# rx.net
KiCad netlist of a schematic drawn in EAGLE
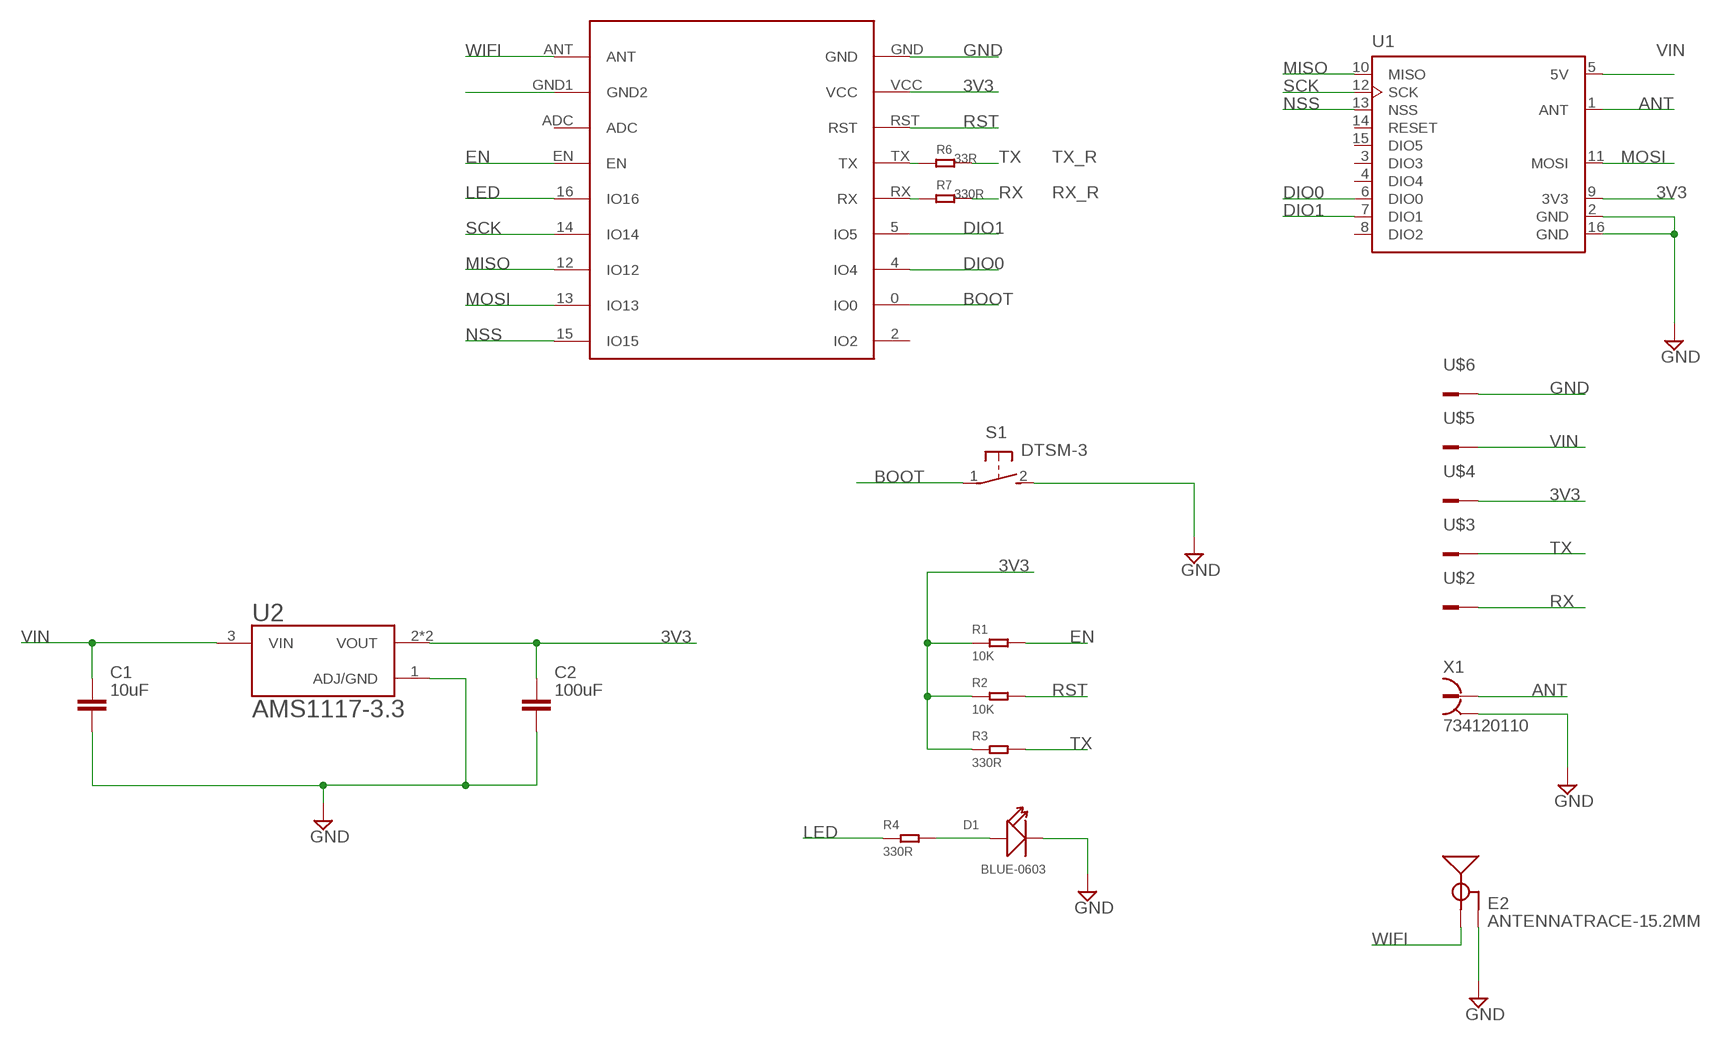
[diagram p0: schematic, sheet 1]

(export (version "E")
  (design (tool "Eeschema 10.0.6"))
  (components
    (comp (ref "C1")
      (value "10uF")
      (footprint "eagle-import:CAPM3528X210")
      (libsource (lib "eagle-import") (part "CTANTALUM-1411(3528-METRIC)_"))
    )
    (comp (ref "C2")
      (value "100uF")
      (footprint "eagle-import:CAPM3528X210")
      (libsource (lib "eagle-import") (part "CTANTALUM-1411(3528-METRIC)_"))
    )
    (comp (ref "D1")
      (value "BLUE-0603")
      (footprint "eagle-import:LED-0603")
      (fields (field (name "MPN") "19-217-BHC-ZL1M2RY-3T"))
      (libsource (lib "eagle-import") (part "SMD-LED-CLEAR-BLUE(0603)"))
    )
    (comp (ref "E2")
      (value "ANTENNATRACE-15.2MM")
      (footprint "eagle-import:TRACE_ANTENNA_2.4GHZ_15.2MM")
      (libsource (lib "eagle-import") (part "ANTENNATRACE-15.2MM"))
    )
    (comp (ref "R1")
      (value "10K")
      (footprint "eagle-import:R0805")
      (fields (field (name "MPN") "RC0805FR-0710KL"))
      (libsource (lib "eagle-import") (part "SMD-RES-10K-1%-1/8W(0805)"))
    )
    (comp (ref "R2")
      (value "10K")
      (footprint "eagle-import:R0805")
      (fields (field (name "MPN") "RC0805FR-0710KL"))
      (libsource (lib "eagle-import") (part "SMD-RES-10K-1%-1/8W(0805)"))
    )
    (comp (ref "R3")
      (value "330R")
      (footprint "eagle-import:R0805")
      (fields (field (name "MPN") "RC0805JR-071KL"))
      (libsource (lib "eagle-import") (part "SMD-RES-330R-5%-1/8W(0805)"))
    )
    (comp (ref "R4")
      (value "330R")
      (footprint "eagle-import:R0805")
      (fields (field (name "MPN") "RC0805JR-071KL"))
      (libsource (lib "eagle-import") (part "SMD-RES-330R-5%-1/8W(0805)"))
    )
    (comp (ref "R6")
      (value "33R")
      (footprint "eagle-import:R0805")
      (fields (field (name "MPN") "RC0805JR-071KL"))
      (libsource (lib "eagle-import") (part "SMD-RES-330R-5%-1/8W(0805)"))
    )
    (comp (ref "R7")
      (value "330R")
      (footprint "eagle-import:R0805")
      (fields (field (name "MPN") "RC0805JR-071KL"))
      (libsource (lib "eagle-import") (part "SMD-RES-330R-5%-1/8W(0805)"))
    )
    (comp (ref "S1")
      (value "DTSM-3")
      (footprint "eagle-import:DTSM-3")
      (libsource (lib "eagle-import") (part "DTSM-3"))
    )
    (comp (ref "U$1")
      (value "ESP-M2")
      (footprint "eagle-import:ESP-M2")
      (fields
        (field (name "MF") "Doctors of Intelligence & Technology Co., LTD")
        (field (name "MP") " ESP-M2 ")
      )
      (libsource (lib "eagle-import") (part "ESP-M2"))
    )
    (comp (ref "U$2")
      (value "CONN-1")
      (footprint "eagle-import:PAD1")
      (libsource (lib "eagle-import") (part "CONN-1"))
    )
    (comp (ref "U$3")
      (value "CONN-1")
      (footprint "eagle-import:PAD1")
      (libsource (lib "eagle-import") (part "CONN-1"))
    )
    (comp (ref "U$4")
      (value "CONN-1")
      (footprint "eagle-import:PAD1")
      (libsource (lib "eagle-import") (part "CONN-1"))
    )
    (comp (ref "U$5")
      (value "CONN-1")
      (footprint "eagle-import:PAD1")
      (libsource (lib "eagle-import") (part "CONN-1"))
    )
    (comp (ref "U$6")
      (value "CONN-1")
      (footprint "eagle-import:PAD1")
      (libsource (lib "eagle-import") (part "CONN-1"))
    )
    (comp (ref "U1")
      (value "RFM95PW-868S2PW")
      (footprint "eagle-import:XCVR_RFM95PW-868S2")
      (libsource (lib "eagle-import") (part "RFM95PW-868S2PW"))
    )
    (comp (ref "U2")
      (value "AMS1117-3.3")
      (footprint "eagle-import:SOT229P700X180-4N")
      (fields (field (name "MF") "Advanced Monolithic Systems"))
      (libsource (lib "eagle-import") (part "AMS1117-3.3"))
    )
    (comp (ref "X1")
      (value "734120110")
      (footprint "eagle-import:734120110")
      (fields (field (name "MF") "Molex") (field (name "MP") "734-12-0110"))
      (libsource (lib "eagle-import") (part "734120110"))
    )
  )
  (nets
    (net (code "1") (name "/3V3") (class "Default")
      (node (ref "C2") (pin "1") (pinfunction "1_1") (pintype "passive"))
      (node (ref "R1") (pin "1") (pinfunction "1_1") (pintype "passive"))
      (node (ref "R2") (pin "1") (pinfunction "1_1") (pintype "passive"))
      (node (ref "R3") (pin "1") (pinfunction "1_1") (pintype "passive"))
      (node (ref "U$1") (pin "VCC") (pinfunction "VCC_VCC") (pintype "bidirectional"))
      (node (ref "U$4") (pin "P$1") (pinfunction "1_P$1") (pintype "passive"))
      (node (ref "U1") (pin "9") (pinfunction "3V3_9") (pintype "power_in"))
      (node (ref "U2") (pin "2") (pinfunction "VOUT_2") (pintype "output"))
      (node (ref "U2") (pin "4") (pinfunction "VOUT_4") (pintype "output"))
    )
    (net (code "2") (name "/ANT") (class "Default")
      (node (ref "U1") (pin "1") (pinfunction "ANT_1") (pintype "passive"))
      (node (ref "X1") (pin "1") (pinfunction "1_1") (pintype "passive"))
    )
    (net (code "3") (name "/BOOT") (class "Default")
      (node (ref "S1") (pin "1") (pinfunction "1_1") (pintype "passive"))
      (node (ref "U$1") (pin "0") (pinfunction "IO0_0") (pintype "bidirectional"))
    )
    (net (code "4") (name "/DIO0") (class "Default")
      (node (ref "U$1") (pin "4") (pinfunction "IO4_4") (pintype "bidirectional"))
      (node (ref "U1") (pin "6") (pinfunction "DIO0_6") (pintype "bidirectional"))
    )
    (net (code "5") (name "/DIO1") (class "Default")
      (node (ref "U$1") (pin "5") (pinfunction "IO5_5") (pintype "bidirectional"))
      (node (ref "U1") (pin "7") (pinfunction "DIO1_7") (pintype "bidirectional"))
    )
    (net (code "6") (name "/EN") (class "Default")
      (node (ref "R1") (pin "2") (pinfunction "2_2") (pintype "passive"))
      (node (ref "U$1") (pin "EN") (pinfunction "EN_EN") (pintype "bidirectional"))
    )
    (net (code "7") (name "/LED") (class "Default")
      (node (ref "R4") (pin "1") (pinfunction "1_1") (pintype "passive"))
      (node (ref "U$1") (pin "16") (pinfunction "IO16_16") (pintype "bidirectional"))
    )
    (net (code "8") (name "/MISO") (class "Default")
      (node (ref "U$1") (pin "12") (pinfunction "IO12_12") (pintype "bidirectional"))
      (node (ref "U1") (pin "10") (pinfunction "MISO_10") (pintype "input"))
    )
    (net (code "9") (name "/MOSI") (class "Default")
      (node (ref "U$1") (pin "13") (pinfunction "IO13_13") (pintype "bidirectional"))
      (node (ref "U1") (pin "11") (pinfunction "MOSI_11") (pintype "output"))
    )
    (net (code "10") (name "/NSS") (class "Default")
      (node (ref "U$1") (pin "15") (pinfunction "IO15_15") (pintype "bidirectional"))
      (node (ref "U1") (pin "13") (pinfunction "NSS_13") (pintype "input"))
    )
    (net (code "11") (name "/RST") (class "Default")
      (node (ref "R2") (pin "2") (pinfunction "2_2") (pintype "passive"))
      (node (ref "U$1") (pin "RST") (pinfunction "RST_RST") (pintype "bidirectional"))
    )
    (net (code "12") (name "/RX") (class "Default")
      (node (ref "R7") (pin "2") (pinfunction "2_2") (pintype "passive"))
      (node (ref "U$2") (pin "P$1") (pinfunction "1_P$1") (pintype "passive"))
    )
    (net (code "13") (name "/RX_R") (class "Default")
      (node (ref "R7") (pin "1") (pinfunction "1_1") (pintype "passive"))
      (node (ref "U$1") (pin "RX") (pinfunction "RX_RX") (pintype "bidirectional"))
    )
    (net (code "14") (name "/SCK") (class "Default")
      (node (ref "U$1") (pin "14") (pinfunction "IO14_14") (pintype "bidirectional"))
      (node (ref "U1") (pin "12") (pinfunction "SCK_12") (pintype "input"))
    )
    (net (code "15") (name "/TX") (class "Default")
      (node (ref "R3") (pin "2") (pinfunction "2_2") (pintype "passive"))
      (node (ref "R6") (pin "2") (pinfunction "2_2") (pintype "passive"))
      (node (ref "U$3") (pin "P$1") (pinfunction "1_P$1") (pintype "passive"))
    )
    (net (code "16") (name "/TX_R") (class "Default")
      (node (ref "R6") (pin "1") (pinfunction "1_1") (pintype "passive"))
      (node (ref "U$1") (pin "TX") (pinfunction "TX_TX") (pintype "bidirectional"))
    )
    (net (code "17") (name "/VIN") (class "Default")
      (node (ref "C1") (pin "1") (pinfunction "1_1") (pintype "passive"))
      (node (ref "U$5") (pin "P$1") (pinfunction "1_P$1") (pintype "passive"))
      (node (ref "U1") (pin "5") (pinfunction "5V_5") (pintype "power_in"))
      (node (ref "U2") (pin "3") (pinfunction "VIN_3") (pintype "input"))
    )
    (net (code "18") (name "/WIFI") (class "Default")
      (node (ref "E2") (pin "ANT") (pinfunction "SIGNAL_ANT") (pintype "bidirectional"))
      (node (ref "U$1") (pin "ANT") (pinfunction "ANT_ANT") (pintype "bidirectional"))
    )
    (net (code "19") (name "GND") (class "Default")
      (node (ref "C1") (pin "2") (pinfunction "2_2") (pintype "passive"))
      (node (ref "C2") (pin "2") (pinfunction "2_2") (pintype "passive"))
      (node (ref "D1") (pin "-") (pinfunction "-_-") (pintype "passive"))
      (node (ref "E2") (pin "GND") (pinfunction "GND_GND") (pintype "bidirectional"))
      (node (ref "S1") (pin "2") (pinfunction "2_2") (pintype "passive"))
      (node (ref "U$1") (pin "GND") (pinfunction "GND_GND") (pintype "bidirectional"))
      (node (ref "U$1") (pin "GND1") (pinfunction "GND2_GND1") (pintype "bidirectional"))
      (node (ref "U$6") (pin "P$1") (pinfunction "1_P$1") (pintype "passive"))
      (node (ref "U1") (pin "16") (pinfunction "GND_16") (pintype "power_in"))
      (node (ref "U1") (pin "2") (pinfunction "GND_2") (pintype "power_in"))
      (node (ref "U2") (pin "1") (pinfunction "ADJ/GND_1") (pintype "power_in"))
      (node (ref "X1") (pin "S@1") (pinfunction "2_S@1") (pintype "passive"))
      (node (ref "X1") (pin "S@2") (pinfunction "2_S@2") (pintype "passive"))
      (node (ref "X1") (pin "S@3") (pinfunction "2_S@3") (pintype "passive"))
    )
    (net (code "20") (name "Net-(D1-Pad+)") (class "Default")
      (node (ref "D1") (pin "+") (pinfunction "+_+") (pintype "passive"))
      (node (ref "R4") (pin "2") (pinfunction "2_2") (pintype "passive"))
    )
    (net (code "21") (name "unconnected-(U$1-IO2-Pad2)") (class "Default")
      (node (ref "U$1") (pin "2") (pinfunction "IO2_2") (pintype "bidirectional"))
    )
    (net (code "22") (name "unconnected-(U$1-PadADC)") (class "Default")
      (node (ref "U$1") (pin "ADC") (pinfunction "ADC_ADC") (pintype "bidirectional"))
    )
    (net (code "23") (name "unconnected-(U1-DIO2-Pad8)") (class "Default")
      (node (ref "U1") (pin "8") (pinfunction "DIO2_8") (pintype "bidirectional"))
    )
    (net (code "24") (name "unconnected-(U1-DIO3-Pad3)") (class "Default")
      (node (ref "U1") (pin "3") (pinfunction "DIO3_3") (pintype "bidirectional"))
    )
    (net (code "25") (name "unconnected-(U1-DIO4-Pad4)") (class "Default")
      (node (ref "U1") (pin "4") (pinfunction "DIO4_4") (pintype "bidirectional"))
    )
    (net (code "26") (name "unconnected-(U1-DIO5-Pad15)") (class "Default")
      (node (ref "U1") (pin "15") (pinfunction "DIO5_15") (pintype "bidirectional"))
    )
    (net (code "27") (name "unconnected-(U1-RESET-Pad14)") (class "Default")
      (node (ref "U1") (pin "14") (pinfunction "RESET_14") (pintype "bidirectional"))
    )
  )
)
